# esp07_ups.net
KiCad netlist of a schematic drawn in EAGLE
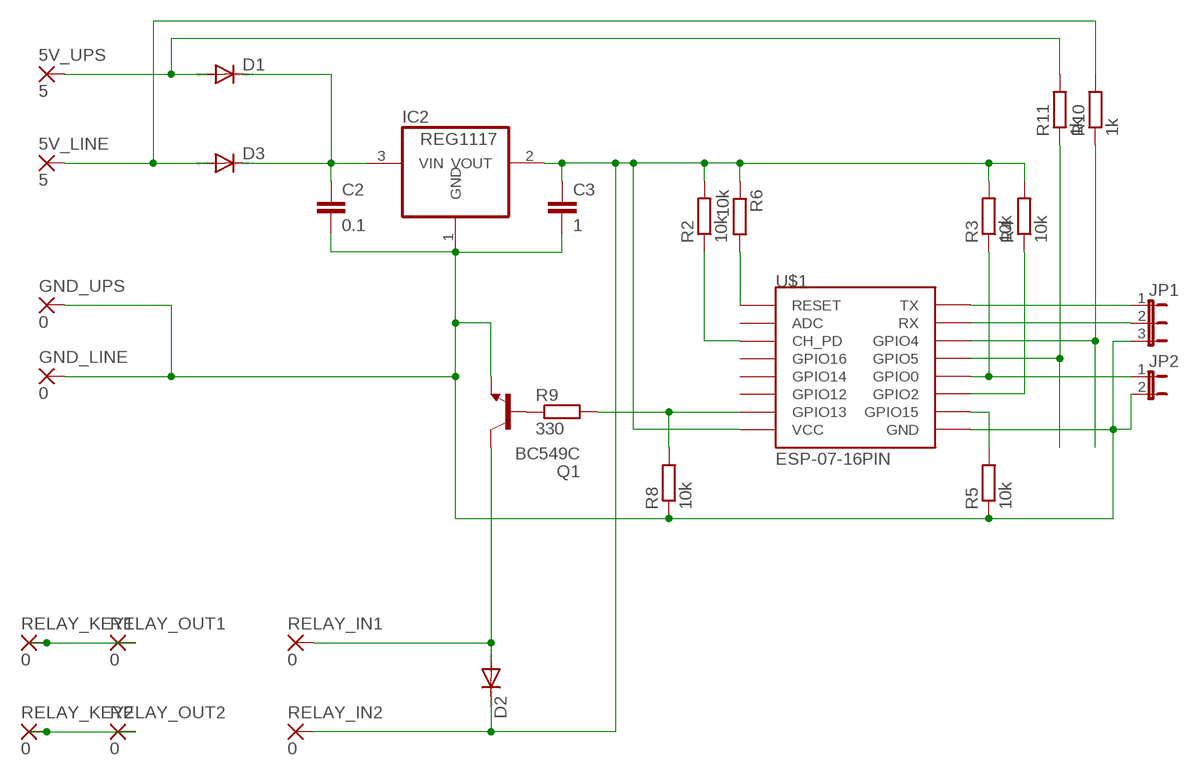
[diagram p0: schematic, sheet 1]

(export (version "E")
  (design (tool "Eeschema 10.0.6"))
  (components
    (comp (ref "5V_LINE")
      (value "5")
      (footprint "eagle-import:2,15_1,0")
      (libsource (lib "eagle-import") (part "2,15/1,0"))
    )
    (comp (ref "5V_UPS")
      (value "5")
      (footprint "eagle-import:2,15_1,0")
      (libsource (lib "eagle-import") (part "2,15/1,0"))
    )
    (comp (ref "C2")
      (value "0.1")
      (footprint "eagle-import:C0805")
      (libsource (lib "eagle-import") (part "C-EUC0805"))
    )
    (comp (ref "C3")
      (value "1")
      (footprint "eagle-import:C0805")
      (libsource (lib "eagle-import") (part "C-EUC0805"))
    )
    (comp (ref "D1")
      (value "DIODE-SOD80C")
      (footprint "eagle-import:SOD80C")
      (libsource (lib "eagle-import") (part "DIODE-SOD80C"))
    )
    (comp (ref "D2")
      (value "DIODE-SOD80C")
      (footprint "eagle-import:SOD80C")
      (libsource (lib "eagle-import") (part "DIODE-SOD80C"))
    )
    (comp (ref "D3")
      (value "DIODE-SOD80C")
      (footprint "eagle-import:SOD80C")
      (libsource (lib "eagle-import") (part "DIODE-SOD80C"))
    )
    (comp (ref "GND_LINE")
      (value "0")
      (footprint "eagle-import:2,15_1,0")
      (libsource (lib "eagle-import") (part "2,15/1,0"))
    )
    (comp (ref "GND_UPS")
      (value "0")
      (footprint "eagle-import:2,15_1,0")
      (libsource (lib "eagle-import") (part "2,15/1,0"))
    )
    (comp (ref "IC2")
      (value "REG1117")
      (footprint "eagle-import:SOT223")
      (libsource (lib "eagle-import") (part "REG1117"))
    )
    (comp (ref "JP1")
      (value "JP2E")
      (footprint "eagle-import:JP2")
      (libsource (lib "eagle-import") (part "JP2E"))
    )
    (comp (ref "JP2")
      (value "JP1E")
      (footprint "eagle-import:JP1")
      (libsource (lib "eagle-import") (part "JP1E"))
    )
    (comp (ref "Q1")
      (value "BC549C")
      (footprint "eagle-import:TO92-EBC")
      (libsource (lib "eagle-import") (part "BC549C"))
    )
    (comp (ref "R2")
      (value "10k")
      (footprint "eagle-import:R1206")
      (libsource (lib "eagle-import") (part "R-EU_R1206"))
    )
    (comp (ref "R3")
      (value "10k")
      (footprint "eagle-import:R1206")
      (libsource (lib "eagle-import") (part "R-EU_R1206"))
    )
    (comp (ref "R4")
      (value "10k")
      (footprint "eagle-import:R1206")
      (libsource (lib "eagle-import") (part "R-EU_R1206"))
    )
    (comp (ref "R5")
      (value "10k")
      (footprint "eagle-import:R1206")
      (libsource (lib "eagle-import") (part "R-EU_R1206"))
    )
    (comp (ref "R6")
      (value "10k")
      (footprint "eagle-import:R1206")
      (libsource (lib "eagle-import") (part "R-EU_R1206"))
    )
    (comp (ref "R8")
      (value "10k")
      (footprint "eagle-import:R1206")
      (libsource (lib "eagle-import") (part "R-EU_R1206"))
    )
    (comp (ref "R9")
      (value "330")
      (footprint "eagle-import:R1206")
      (libsource (lib "eagle-import") (part "R-EU_R1206"))
    )
    (comp (ref "R10")
      (value "1k")
      (footprint "eagle-import:R1206")
      (libsource (lib "eagle-import") (part "R-EU_R1206"))
    )
    (comp (ref "R11")
      (value "1k")
      (footprint "eagle-import:R1206")
      (libsource (lib "eagle-import") (part "R-EU_R1206"))
    )
    (comp (ref "RELAY_IN1")
      (value "0")
      (footprint "eagle-import:3,17_1,1")
      (libsource (lib "eagle-import") (part "3,17/1,1"))
    )
    (comp (ref "RELAY_IN2")
      (value "0")
      (footprint "eagle-import:3,17_1,1")
      (libsource (lib "eagle-import") (part "3,17/1,1"))
    )
    (comp (ref "RELAY_KEY1")
      (value "0")
      (footprint "eagle-import:2,15_1,0")
      (libsource (lib "eagle-import") (part "2,15/1,0"))
    )
    (comp (ref "RELAY_KEY2")
      (value "0")
      (footprint "eagle-import:2,15_1,0")
      (libsource (lib "eagle-import") (part "2,15/1,0"))
    )
    (comp (ref "RELAY_OUT1")
      (value "0")
      (footprint "eagle-import:3,17_1,1")
      (libsource (lib "eagle-import") (part "3,17/1,1"))
    )
    (comp (ref "RELAY_OUT2")
      (value "0")
      (footprint "eagle-import:3,17_1,1")
      (libsource (lib "eagle-import") (part "3,17/1,1"))
    )
    (comp (ref "U$1")
      (value "ESP-07-16PIN")
      (footprint "eagle-import:ESP-07-16PIN")
      (libsource (lib "eagle-import") (part "ESP-07-16PIN"))
    )
  )
  (nets
    (net (code "1") (name "Net-(5V_LINE-P)") (class "Default")
      (node (ref "5V_LINE") (pin "1") (pinfunction "P_1") (pintype "passive"))
      (node (ref "D3") (pin "A") (pinfunction "A_A") (pintype "passive"))
      (node (ref "R10") (pin "2") (pinfunction "2_2") (pintype "passive"))
    )
    (net (code "2") (name "Net-(5V_UPS-P)") (class "Default")
      (node (ref "5V_UPS") (pin "1") (pinfunction "P_1") (pintype "passive"))
      (node (ref "D1") (pin "A") (pinfunction "A_A") (pintype "passive"))
      (node (ref "R11") (pin "2") (pinfunction "2_2") (pintype "passive"))
    )
    (net (code "3") (name "Net-(GND_LINE-P)") (class "Default")
      (node (ref "C2") (pin "2") (pinfunction "2_2") (pintype "passive"))
      (node (ref "C3") (pin "2") (pinfunction "2_2") (pintype "passive"))
      (node (ref "GND_LINE") (pin "1") (pinfunction "P_1") (pintype "passive"))
      (node (ref "GND_UPS") (pin "1") (pinfunction "P_1") (pintype "passive"))
      (node (ref "IC2") (pin "1") (pinfunction "GND_1") (pintype "power_in"))
      (node (ref "JP1") (pin "3") (pinfunction "3_3") (pintype "passive"))
      (node (ref "JP2") (pin "2") (pinfunction "2_2") (pintype "passive"))
      (node (ref "Q1") (pin "E") (pinfunction "E_E") (pintype "passive"))
      (node (ref "R5") (pin "1") (pinfunction "1_1") (pintype "passive"))
      (node (ref "R8") (pin "1") (pinfunction "1_1") (pintype "passive"))
      (node (ref "U$1") (pin "GND") (pinfunction "GND_GND") (pintype "bidirectional"))
    )
    (net (code "4") (name "Net-(IC2-VIN)") (class "Default")
      (node (ref "C2") (pin "1") (pinfunction "1_1") (pintype "passive"))
      (node (ref "D1") (pin "C") (pinfunction "C_C") (pintype "passive"))
      (node (ref "D3") (pin "C") (pinfunction "C_C") (pintype "passive"))
      (node (ref "IC2") (pin "3") (pinfunction "VIN_3") (pintype "input"))
    )
    (net (code "5") (name "Net-(IC2-VOUT)") (class "Default")
      (node (ref "C3") (pin "1") (pinfunction "1_1") (pintype "passive"))
      (node (ref "D2") (pin "C") (pinfunction "C_C") (pintype "passive"))
      (node (ref "IC2") (pin "2") (pinfunction "VOUT_2") (pintype "output"))
      (node (ref "R2") (pin "2") (pinfunction "2_2") (pintype "passive"))
      (node (ref "R3") (pin "2") (pinfunction "2_2") (pintype "passive"))
      (node (ref "R4") (pin "2") (pinfunction "2_2") (pintype "passive"))
      (node (ref "R6") (pin "1") (pinfunction "1_1") (pintype "passive"))
      (node (ref "RELAY_IN2") (pin "1") (pinfunction "P_1") (pintype "passive"))
      (node (ref "U$1") (pin "VCC") (pinfunction "VCC_VCC") (pintype "bidirectional"))
    )
    (net (code "6") (name "Net-(JP1-Pad1)") (class "Default")
      (node (ref "JP1") (pin "1") (pinfunction "1_1") (pintype "passive"))
      (node (ref "U$1") (pin "TX") (pinfunction "TX_TX") (pintype "bidirectional"))
    )
    (net (code "7") (name "Net-(JP1-Pad2)") (class "Default")
      (node (ref "JP1") (pin "2") (pinfunction "2_2") (pintype "passive"))
      (node (ref "U$1") (pin "RX") (pinfunction "RX_RX") (pintype "bidirectional"))
    )
    (net (code "8") (name "Net-(JP2-Pad1)") (class "Default")
      (node (ref "JP2") (pin "1") (pinfunction "1_1") (pintype "passive"))
      (node (ref "R3") (pin "1") (pinfunction "1_1") (pintype "passive"))
      (node (ref "U$1") (pin "GPIO0") (pinfunction "GPIO0_GPIO0") (pintype "bidirectional"))
    )
    (net (code "9") (name "Net-(Q1-PadB)") (class "Default")
      (node (ref "Q1") (pin "B") (pinfunction "B_B") (pintype "passive"))
      (node (ref "R9") (pin "1") (pinfunction "1_1") (pintype "passive"))
    )
    (net (code "10") (name "Net-(R2-Pad1)") (class "Default")
      (node (ref "R2") (pin "1") (pinfunction "1_1") (pintype "passive"))
      (node (ref "U$1") (pin "CH_PD") (pinfunction "CH_PD_CH_PD") (pintype "bidirectional"))
    )
    (net (code "11") (name "Net-(R4-Pad1)") (class "Default")
      (node (ref "R4") (pin "1") (pinfunction "1_1") (pintype "passive"))
      (node (ref "U$1") (pin "GPIO2") (pinfunction "GPIO2_GPIO2") (pintype "bidirectional"))
    )
    (net (code "12") (name "Net-(R5-Pad2)") (class "Default")
      (node (ref "R5") (pin "2") (pinfunction "2_2") (pintype "passive"))
      (node (ref "U$1") (pin "GPIO15") (pinfunction "GPIO15_GPIO15") (pintype "bidirectional"))
    )
    (net (code "13") (name "Net-(R8-Pad2)") (class "Default")
      (node (ref "R8") (pin "2") (pinfunction "2_2") (pintype "passive"))
      (node (ref "R9") (pin "2") (pinfunction "2_2") (pintype "passive"))
      (node (ref "U$1") (pin "GPIO13") (pinfunction "GPIO13_GPIO13") (pintype "bidirectional"))
    )
    (net (code "14") (name "Net-(R10-Pad1)") (class "Default")
      (node (ref "R10") (pin "1") (pinfunction "1_1") (pintype "passive"))
      (node (ref "U$1") (pin "GPIO4") (pinfunction "GPIO4_GPIO4") (pintype "bidirectional"))
    )
    (net (code "15") (name "Net-(R11-Pad1)") (class "Default")
      (node (ref "R11") (pin "1") (pinfunction "1_1") (pintype "passive"))
      (node (ref "U$1") (pin "GPIO5") (pinfunction "GPIO5_GPIO5") (pintype "bidirectional"))
    )
    (net (code "16") (name "Net-(RELAY_IN1-P)") (class "Default")
      (node (ref "D2") (pin "A") (pinfunction "A_A") (pintype "passive"))
      (node (ref "Q1") (pin "C") (pinfunction "C_C") (pintype "passive"))
      (node (ref "RELAY_IN1") (pin "1") (pinfunction "P_1") (pintype "passive"))
    )
    (net (code "17") (name "Net-(RELAY_KEY1-P)") (class "Default")
      (node (ref "RELAY_KEY1") (pin "1") (pinfunction "P_1") (pintype "passive"))
      (node (ref "RELAY_OUT1") (pin "1") (pinfunction "P_1") (pintype "passive"))
    )
    (net (code "18") (name "Net-(RELAY_KEY2-P)") (class "Default")
      (node (ref "RELAY_KEY2") (pin "1") (pinfunction "P_1") (pintype "passive"))
      (node (ref "RELAY_OUT2") (pin "1") (pinfunction "P_1") (pintype "passive"))
    )
    (net (code "19") (name "Net-(U$1-RESET)") (class "Default")
      (node (ref "R6") (pin "2") (pinfunction "2_2") (pintype "passive"))
      (node (ref "U$1") (pin "REST") (pinfunction "RESET_REST") (pintype "bidirectional"))
    )
    (net (code "20") (name "unconnected-(U$1-PadADC)") (class "Default")
      (node (ref "U$1") (pin "ADC") (pinfunction "ADC_ADC") (pintype "bidirectional"))
    )
    (net (code "21") (name "unconnected-(U$1-PadGPIO12)") (class "Default")
      (node (ref "U$1") (pin "GPIO12") (pinfunction "GPIO12_GPIO12") (pintype "bidirectional"))
    )
    (net (code "22") (name "unconnected-(U$1-PadGPIO14)") (class "Default")
      (node (ref "U$1") (pin "GPIO14") (pinfunction "GPIO14_GPIO14") (pintype "bidirectional"))
    )
    (net (code "23") (name "unconnected-(U$1-PadGPIO16)") (class "Default")
      (node (ref "U$1") (pin "GPIO16") (pinfunction "GPIO16_GPIO16") (pintype "bidirectional"))
    )
  )
)
